# BatteryPCB2997.net
KiCad netlist of a schematic drawn in EAGLE
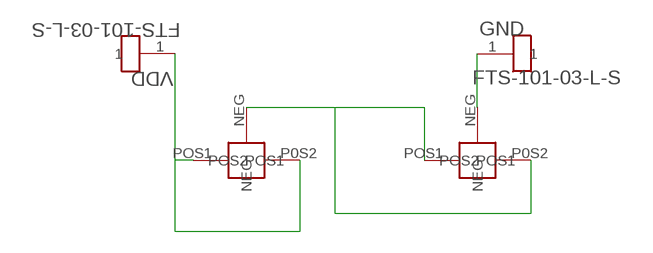
[diagram p0: schematic, sheet 1]

(export (version "E")
  (design (tool "Eeschema 10.0.6"))
  (components
    (comp (ref "GND")
      (value "FTS-101-03-L-S")
      (footprint "eagle-import:SAMTEC_FTS-101-03-S")
      (libsource (lib "eagle-import") (part "FTS-101-03-L-S"))
    )
    (comp (ref "U$3")
      (value "2997")
      (footprint "eagle-import:2997")
      (libsource (lib "eagle-import") (part "2997"))
    )
    (comp (ref "U$4")
      (value "2997")
      (footprint "eagle-import:2997")
      (libsource (lib "eagle-import") (part "2997"))
    )
    (comp (ref "VDD")
      (value "FTS-101-03-L-S")
      (footprint "eagle-import:SAMTEC_FTS-101-03-S")
      (libsource (lib "eagle-import") (part "FTS-101-03-L-S"))
    )
  )
  (nets
    (net (code "1") (name "Net-(GND-Pad1)") (class "Default")
      (node (ref "GND") (pin "1") (pinfunction "1_1") (pintype "passive"))
      (node (ref "U$4") (pin "NEG") (pinfunction "NEG_NEG") (pintype "bidirectional"))
    )
    (net (code "2") (name "Net-(U$3-POS2)") (class "Default")
      (node (ref "U$3") (pin "P0S2") (pinfunction "POS2_P0S2") (pintype "bidirectional"))
      (node (ref "U$3") (pin "POS1") (pinfunction "POS1_POS1") (pintype "bidirectional"))
      (node (ref "VDD") (pin "1") (pinfunction "1_1") (pintype "passive"))
    )
    (net (code "3") (name "Net-(U$4-POS2)") (class "Default")
      (node (ref "U$3") (pin "NEG") (pinfunction "NEG_NEG") (pintype "bidirectional"))
      (node (ref "U$4") (pin "P0S2") (pinfunction "POS2_P0S2") (pintype "bidirectional"))
      (node (ref "U$4") (pin "POS1") (pinfunction "POS1_POS1") (pintype "bidirectional"))
    )
  )
)
